# design.net
KiCad netlist of a schematic drawn in EasyEDA Pro
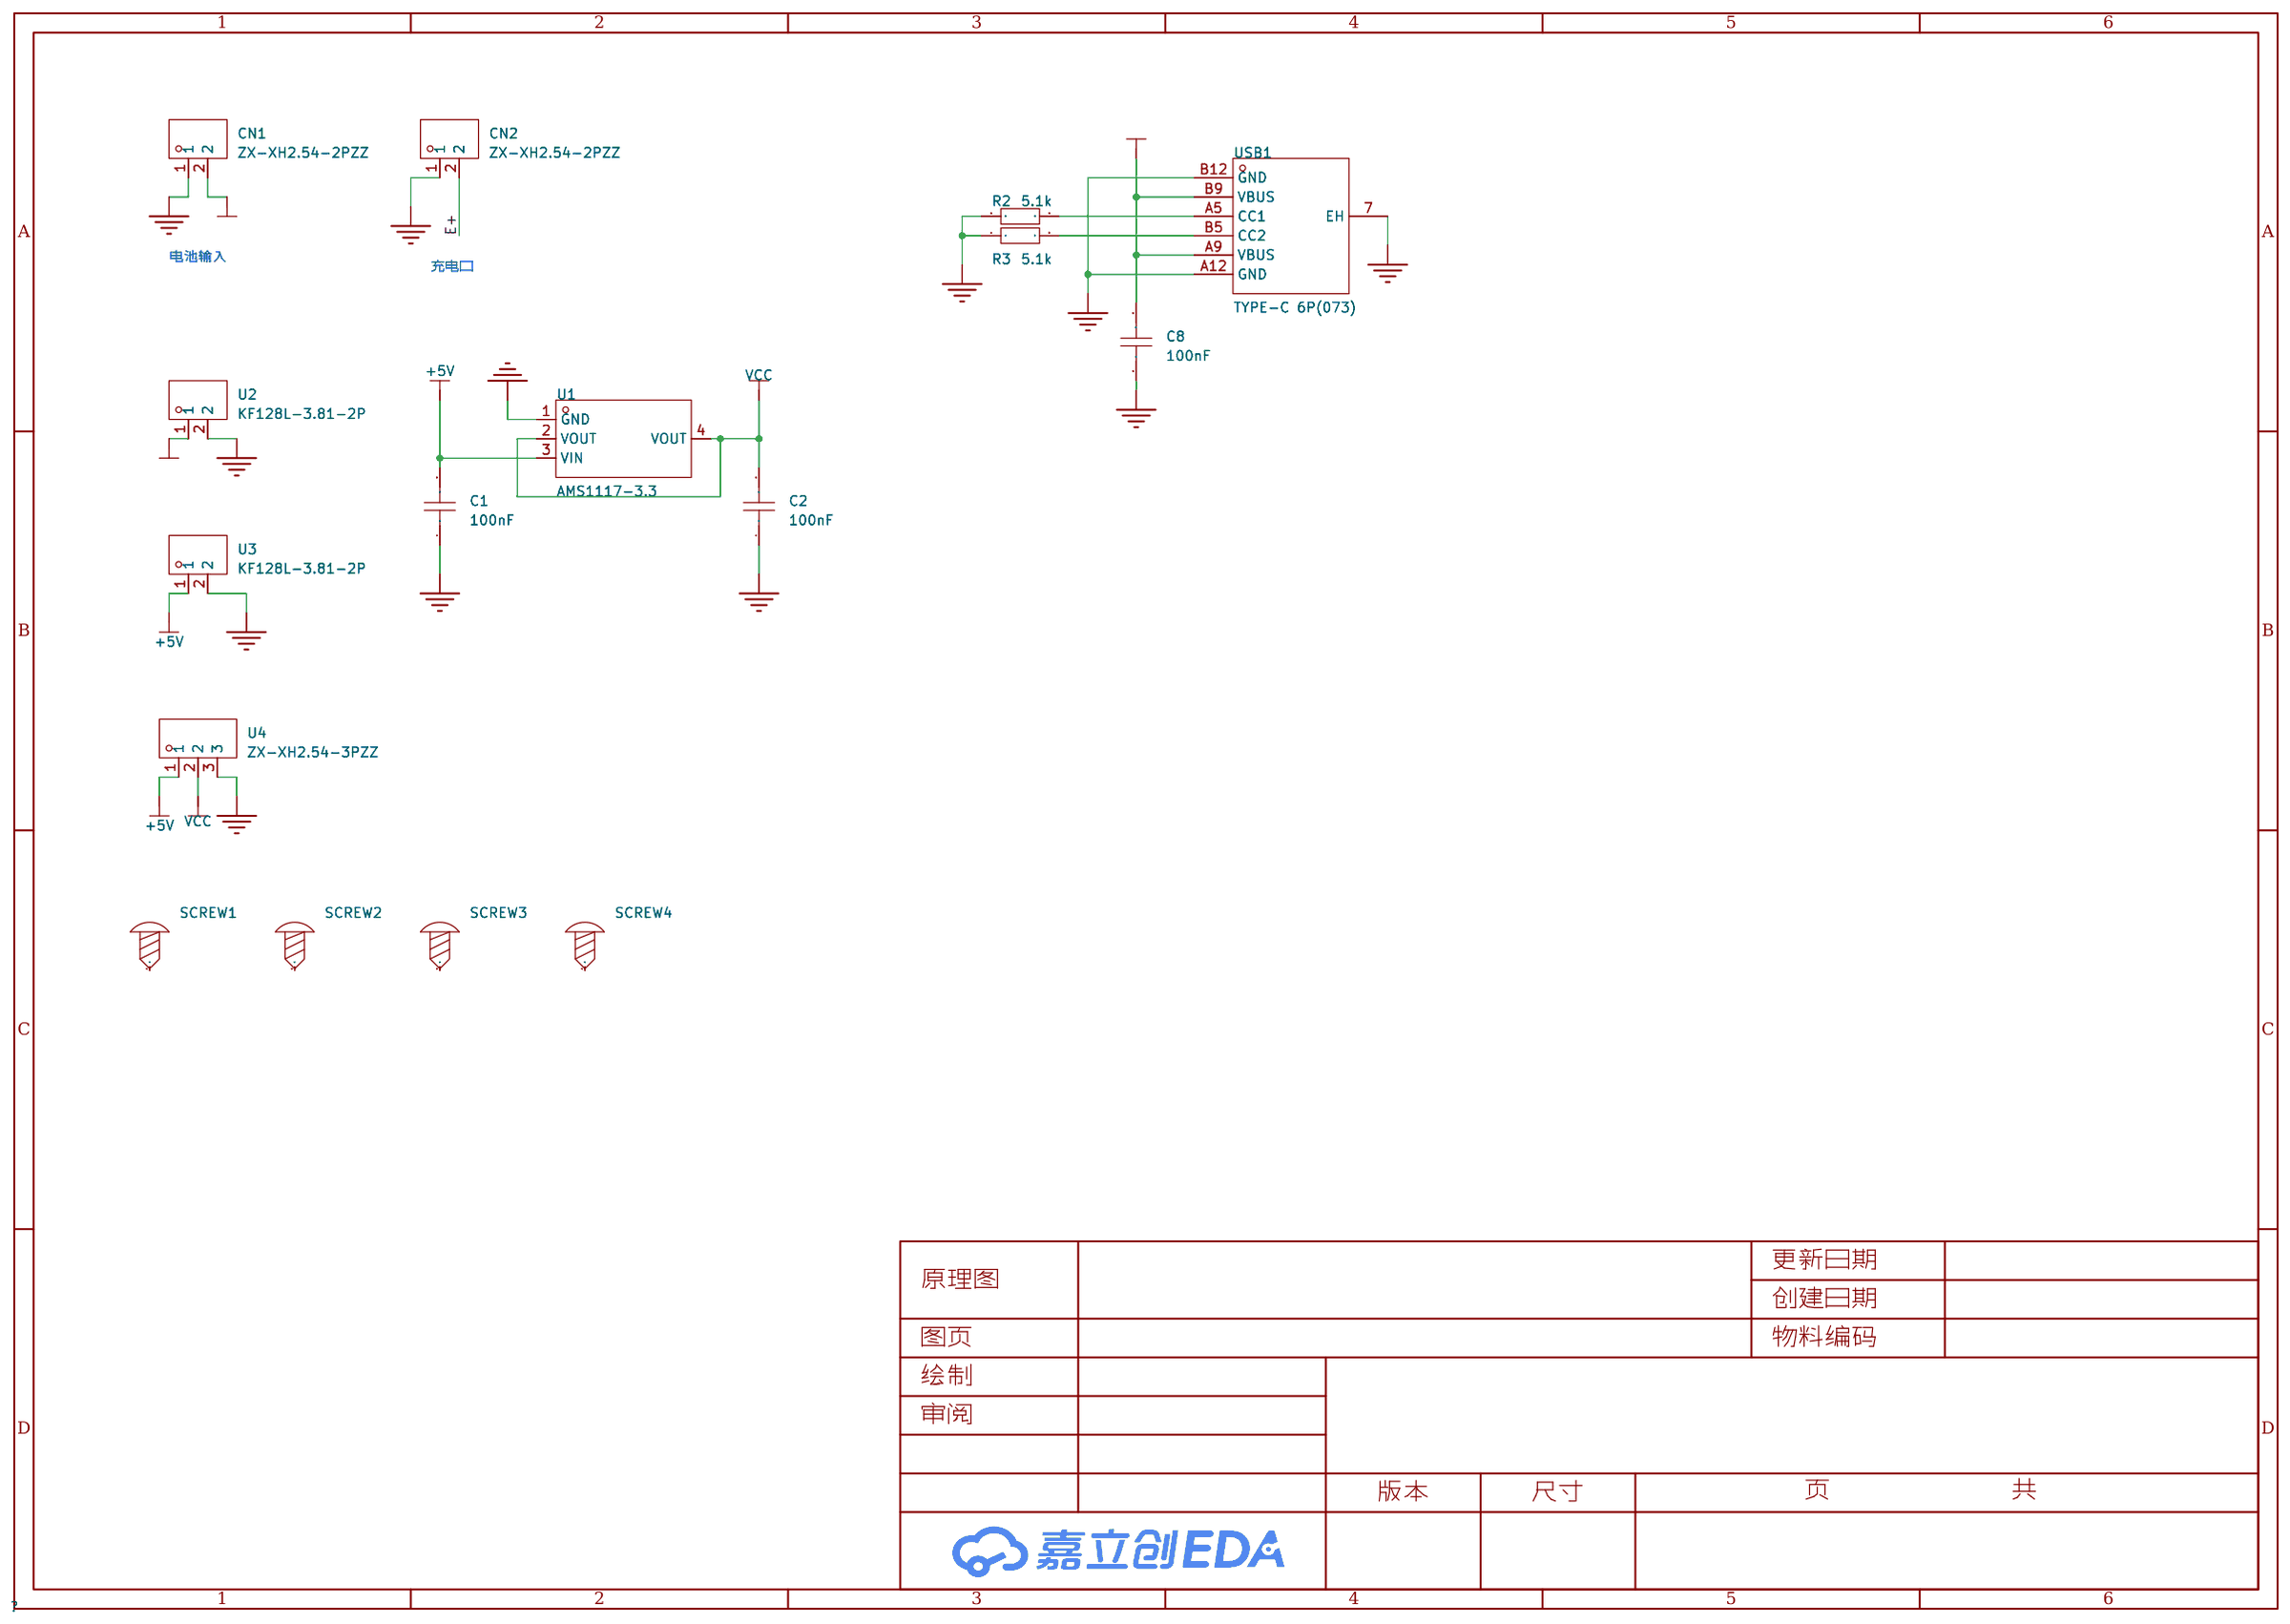
[diagram p0: schematic sheet]

(export (version "E")
  (design (tool "Eeschema 10.0.6"))
  (components
    (comp (ref "C1")
      (value "100nF")
      (footprint "easyedapro:C0603")
      (libsource (lib "easyedapro") (part "CapAcitance"))
    )
    (comp (ref "C2")
      (value "100nF")
      (footprint "easyedapro:C0603")
      (libsource (lib "easyedapro") (part "CapAcitance"))
    )
    (comp (ref "C8")
      (value "100nF")
      (footprint "easyedapro:C0603")
      (libsource (lib "easyedapro") (part "CapAcitance"))
    )
    (comp (ref "CN1")
      (value "ZX-XH2.54-2PZZ")
      (footprint "easyedapro:CONN-TH_2P-P2.50_HX25003-2A")
      (fields (field (name "Manufacturer") "Megastar(兆星)"))
      (libsource (lib "easyedapro") (part "ZX-XH2.54-2PZZ"))
    )
    (comp (ref "CN2")
      (value "ZX-XH2.54-2PZZ")
      (footprint "easyedapro:CONN-TH_2P-P2.50_HX25003-2A")
      (fields (field (name "Manufacturer") "Megastar(兆星)"))
      (libsource (lib "easyedapro") (part "ZX-XH2.54-2PZZ"))
    )
    (comp (ref "R2") (value "5.1k") (footprint "easyedapro:R0603") (libsource (lib "easyedapro") (part "电阻")))
    (comp (ref "R3") (value "5.1k") (footprint "easyedapro:R0603") (libsource (lib "easyedapro") (part "电阻")))
    (comp (ref "SCREW1")
      (value "~")
      (footprint "easyedapro:M3螺丝")
      (libsource (lib "easyedapro") (part "螺丝孔"))
    )
    (comp (ref "SCREW2")
      (value "~")
      (footprint "easyedapro:M3螺丝")
      (libsource (lib "easyedapro") (part "螺丝孔"))
    )
    (comp (ref "SCREW3")
      (value "~")
      (footprint "easyedapro:M3螺丝")
      (libsource (lib "easyedapro") (part "螺丝孔"))
    )
    (comp (ref "SCREW4")
      (value "~")
      (footprint "easyedapro:M3螺丝")
      (libsource (lib "easyedapro") (part "螺丝孔"))
    )
    (comp (ref "U1")
      (value "AMS1117-3.3")
      (footprint "easyedapro:SOT-223-3_L6.5-W3.4-P2.30-LS7.0-BR")
      (description "输出类型:固定;最大输入电压:-;输出电压:3.3V;最大输出电流:1A;电源纹波抑制比(PSRR):72dB@(120Hz);输出极性:正极;")
      (fields (field (name "Manufacturer") "AMS"))
      (libsource (lib "easyedapro") (part "AMS1117-3.3"))
    )
    (comp (ref "U2")
      (value "KF128L-3.81-2P")
      (footprint "easyedapro:CONN-TH_P3.81_KF128L-3.81-2P")
      (fields (field (name "Manufacturer") "KEFA(科发)"))
      (libsource (lib "easyedapro") (part "KF128L-3.81-2P"))
    )
    (comp (ref "U3")
      (value "KF128L-3.81-2P")
      (footprint "easyedapro:CONN-TH_P3.81_KF128L-3.81-2P")
      (fields (field (name "Manufacturer") "KEFA(科发)"))
      (libsource (lib "easyedapro") (part "KF128L-3.81-2P"))
    )
    (comp (ref "U4")
      (value "ZX-XH2.54-3PZZ")
      (footprint "easyedapro:CONN-TH_3P-P2.54_2501S-3P")
      (fields (field (name "Manufacturer") "Megastar(兆星)"))
      (libsource (lib "easyedapro") (part "ZX-XH2.54-3PZZ"))
    )
    (comp (ref "USB1")
      (value "TYPE-C 6P(073)")
      (footprint "easyedapro:TYPE-C-SMD_TYPE-C-6P_5")
      (description "连接器类型:Type-C;标准:-;公母:母;端口数量:1;触点数量:6P;安装方式:卧贴;额定电流 - 电源:5A;工作温度范围:-25°C~+85°C;")
      (fields (field (name "Manufacturer") "SHOU HAN(首韩)"))
      (libsource (lib "easyedapro") (part "TYPE-C 6P(073)"))
    )
  )
  (nets
    (net (code "1") (name "+5V") (class "Default")
      (node (ref "C1") (pin "2") (pinfunction "2_2") (pintype "input"))
      (node (ref "U1") (pin "3") (pinfunction "VIN_3") (pintype "unspecified"))
      (node (ref "U3") (pin "1") (pinfunction "1_1") (pintype "unspecified"))
      (node (ref "U4") (pin "1") (pinfunction "1_1") (pintype "unspecified"))
    )
    (net (code "2") (name "+7.4V") (class "Default")
      (node (ref "CN1") (pin "2") (pinfunction "2_2") (pintype "unspecified"))
      (node (ref "U2") (pin "1") (pinfunction "1_1") (pintype "unspecified"))
    )
    (net (code "3") (name "E+") (class "Default")
      (node (ref "C8") (pin "2") (pinfunction "2_2") (pintype "input"))
      (node (ref "CN2") (pin "2") (pinfunction "2_2") (pintype "unspecified"))
      (node (ref "USB1") (pin "A9") (pinfunction "VBUS_A9") (pintype "unspecified"))
      (node (ref "USB1") (pin "B9") (pinfunction "VBUS_B9") (pintype "unspecified"))
    )
    (net (code "4") (name "GND") (class "Default")
      (node (ref "C1") (pin "1") (pinfunction "1_1") (pintype "input"))
      (node (ref "C2") (pin "1") (pinfunction "1_1") (pintype "input"))
      (node (ref "C8") (pin "1") (pinfunction "1_1") (pintype "input"))
      (node (ref "CN1") (pin "1") (pinfunction "1_1") (pintype "unspecified"))
      (node (ref "CN2") (pin "1") (pinfunction "1_1") (pintype "unspecified"))
      (node (ref "R2") (pin "1") (pinfunction "1_1") (pintype "input"))
      (node (ref "R3") (pin "1") (pinfunction "1_1") (pintype "input"))
      (node (ref "U1") (pin "1") (pinfunction "GND_1") (pintype "unspecified"))
      (node (ref "U2") (pin "2") (pinfunction "2_2") (pintype "unspecified"))
      (node (ref "U3") (pin "2") (pinfunction "2_2") (pintype "unspecified"))
      (node (ref "U4") (pin "3") (pinfunction "3_3") (pintype "unspecified"))
      (node (ref "USB1") (pin "7") (pinfunction "EH_7") (pintype "unspecified"))
      (node (ref "USB1") (pin "A12") (pinfunction "GND_A12") (pintype "unspecified"))
      (node (ref "USB1") (pin "B12") (pinfunction "GND_B12") (pintype "unspecified"))
    )
    (net (code "5") (name "Net-(USB1-CC1)") (class "Default")
      (node (ref "R2") (pin "2") (pinfunction "2_2") (pintype "input"))
      (node (ref "USB1") (pin "A5") (pinfunction "CC1_A5") (pintype "unspecified"))
    )
    (net (code "6") (name "Net-(USB1-CC2)") (class "Default")
      (node (ref "R3") (pin "2") (pinfunction "2_2") (pintype "input"))
      (node (ref "USB1") (pin "B5") (pinfunction "CC2_B5") (pintype "unspecified"))
    )
    (net (code "7") (name "VCC") (class "Default")
      (node (ref "C2") (pin "2") (pinfunction "2_2") (pintype "input"))
      (node (ref "U1") (pin "2") (pinfunction "VOUT_2") (pintype "unspecified"))
      (node (ref "U1") (pin "4") (pinfunction "VOUT_4") (pintype "unspecified"))
      (node (ref "U4") (pin "2") (pinfunction "2_2") (pintype "unspecified"))
    )
    (net (code "8") (name "unconnected-(SCREW1-Pad1)") (class "Default")
      (node (ref "SCREW1") (pin "1") (pinfunction "1_1") (pintype "input"))
    )
    (net (code "9") (name "unconnected-(SCREW2-Pad1)") (class "Default")
      (node (ref "SCREW2") (pin "1") (pinfunction "1_1") (pintype "input"))
    )
    (net (code "10") (name "unconnected-(SCREW3-Pad1)") (class "Default")
      (node (ref "SCREW3") (pin "1") (pinfunction "1_1") (pintype "input"))
    )
    (net (code "11") (name "unconnected-(SCREW4-Pad1)") (class "Default")
      (node (ref "SCREW4") (pin "1") (pinfunction "1_1") (pintype "input"))
    )
  )
)
